# stm8.net
KiCad netlist of a schematic drawn in Altium Designer
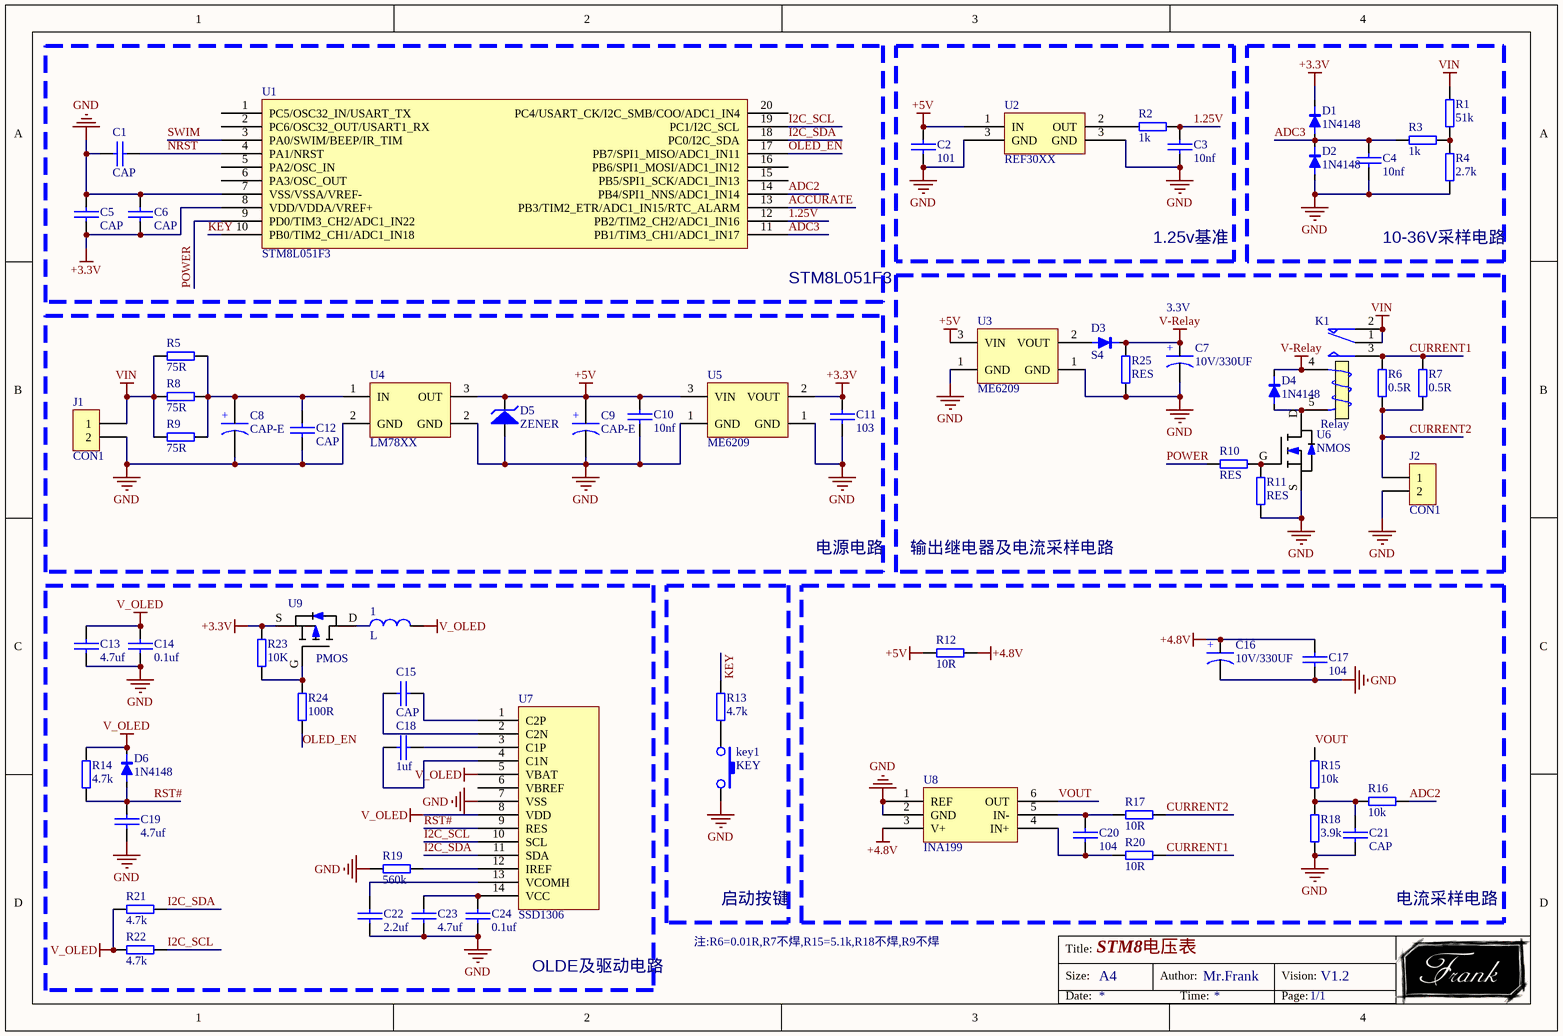
[diagram p0: stm8电压表.SchDoc]

(export (version "E")
  (design (tool "Eeschema 10.0.6"))
  (components
    (comp (ref "1") (value "L") (footprint "0603-R") (libsource (lib "常用元件库") (part "L")))
    (comp (ref "C1") (value "CAP") (footprint "0603-c") (libsource (lib "常用元件库") (part "CAP")))
    (comp (ref "C2") (value "101") (footprint "0603-c") (libsource (lib "常用元件库") (part "CAP")))
    (comp (ref "C3") (value "10nf") (footprint "0603-c") (libsource (lib "常用元件库") (part "CAP")))
    (comp (ref "C4") (value "10nf") (footprint "0603-c") (libsource (lib "常用元件库") (part "CAP")))
    (comp (ref "C5") (value "CAP") (footprint "0603-c") (libsource (lib "常用元件库") (part "CAP")))
    (comp (ref "C6") (value "CAP") (footprint "0603-c") (libsource (lib "常用元件库") (part "CAP")))
    (comp (ref "C7") (value "10V/330UF") (footprint "SMD-EC-F6.3") (libsource (lib "") (part "CAP-E_1")))
    (comp (ref "C8") (value "CAP-E") (footprint "0.1UF") (libsource (lib "常用元件库") (part "CAP-E")))
    (comp (ref "C9") (value "CAP-E") (footprint "SMD-EC-F5") (libsource (lib "常用元件库") (part "CAP-E")))
    (comp (ref "C10") (value "10nf") (footprint "0603-c") (libsource (lib "常用元件库") (part "CAP")))
    (comp (ref "C11") (value "103") (footprint "0603-c") (libsource (lib "常用元件库") (part "CAP")))
    (comp (ref "C12") (value "CAP") (footprint "0603-c") (libsource (lib "常用元件库") (part "CAP")))
    (comp (ref "C13") (value "4.7uf") (footprint "0603-c") (libsource (lib "基本原件库") (part "CAP")))
    (comp (ref "C14") (value "0.1uf") (footprint "0603-c") (libsource (lib "基本原件库") (part "CAP")))
    (comp (ref "C15") (value "CAP") (footprint "0603-c") (libsource (lib "基本原件库") (part "CAP")))
    (comp (ref "C16") (value "10V/330UF") (footprint "SMD-EC-F3") (libsource (lib "") (part "CAP-E_1")))
    (comp (ref "C17") (value "104") (footprint "0603-c") (libsource (lib "常用元件库") (part "CAP")))
    (comp (ref "C18") (value "1uf") (footprint "0603-c") (libsource (lib "基本原件库") (part "CAP")))
    (comp (ref "C19") (value "4.7uf") (footprint "0603-c") (libsource (lib "基本原件库") (part "CAP")))
    (comp (ref "C20") (value "104") (footprint "0603-c") (libsource (lib "常用元件库") (part "CAP")))
    (comp (ref "C21") (value "CAP") (footprint "0603-c") (libsource (lib "常用元件库") (part "CAP")))
    (comp (ref "C22") (value "2.2uf") (footprint "0603-c") (libsource (lib "基本原件库") (part "CAP")))
    (comp (ref "C23") (value "4.7uf") (footprint "0603-c") (libsource (lib "基本原件库") (part "CAP")))
    (comp (ref "C24") (value "0.1uf") (footprint "0603-c") (libsource (lib "基本原件库") (part "CAP")))
    (comp (ref "D1") (value "1N4148") (footprint "SOD-323") (libsource (lib "常用元件库") (part "DIODE1")))
    (comp (ref "D2") (value "1N4148") (footprint "SOD-323") (libsource (lib "常用元件库") (part "DIODE1")))
    (comp (ref "D3") (value "S4") (footprint "SOD-323") (libsource (lib "常用元件库") (part "DIODE1")))
    (comp (ref "D4") (value "1N4148") (footprint "SOD-323") (libsource (lib "常用元件库") (part "DIODE1")))
    (comp (ref "D5") (value "ZENER") (footprint "2512-d") (libsource (lib "常用元件库") (part "ZENER")))
    (comp (ref "D6") (value "1N4148") (footprint "SOD-323") (libsource (lib "常用元件库") (part "DIODE1")))
    (comp (ref "J1") (value "CON1") (footprint "SIP2") (libsource (lib "") (part "CON2_1")))
    (comp (ref "J2") (value "CON1") (footprint "SIP2") (libsource (lib "常用元件库") (part "CON2")))
    (comp (ref "K1")
      (value "Relay")
      (footprint "继电器10.5*15.5")
      (description "SPDT Relay")
      (fields (field (name "PUBLISHER") "Altium Limited"))
      (libsource (lib "Miscellaneous Devices") (part "Relay"))
    )
    (comp (ref "key1") (value "KEY") (footprint "按钮2") (libsource (lib "基本原件库") (part "KEY")))
    (comp (ref "R1") (value "51k") (footprint "0603-r") (libsource (lib "常用元件库") (part "RES")))
    (comp (ref "R2") (value "1k") (footprint "0603-r") (libsource (lib "常用元件库") (part "RES")))
    (comp (ref "R3") (value "1k") (footprint "0603-r") (libsource (lib "常用元件库") (part "RES")))
    (comp (ref "R4") (value "2.7k") (footprint "0603-r") (libsource (lib "常用元件库") (part "RES")))
    (comp (ref "R5") (value "75R") (footprint "2512-d") (libsource (lib "常用元件库") (part "RES")))
    (comp (ref "R6") (value "0.5R") (footprint "2512-D") (libsource (lib "常用元件库") (part "RES")))
    (comp (ref "R7") (value "0.5R") (footprint "2512-D") (libsource (lib "常用元件库") (part "RES")))
    (comp (ref "R8") (value "75R") (footprint "2512-d") (libsource (lib "常用元件库") (part "RES")))
    (comp (ref "R9") (value "75R") (footprint "2512-d") (libsource (lib "常用元件库") (part "RES")))
    (comp (ref "R10") (value "RES") (footprint "0603-r") (libsource (lib "常用元件库") (part "RES")))
    (comp (ref "R11") (value "RES") (footprint "0603-r") (libsource (lib "常用元件库") (part "RES")))
    (comp (ref "R12") (value "10R") (footprint "0603-r") (libsource (lib "常用元件库") (part "RES")))
    (comp (ref "R13") (value "4.7k") (footprint "0603-r") (libsource (lib "基本原件库") (part "RES")))
    (comp (ref "R14") (value "4.7k") (footprint "0603-r") (libsource (lib "基本原件库") (part "RES")))
    (comp (ref "R15") (value "10k") (footprint "0603-r") (libsource (lib "常用元件库") (part "RES")))
    (comp (ref "R16") (value "10k") (footprint "0603-r") (libsource (lib "常用元件库") (part "RES")))
    (comp (ref "R17") (value "10R") (footprint "0603-r") (libsource (lib "常用元件库") (part "RES")))
    (comp (ref "R18") (value "3.9k") (footprint "0603-r") (libsource (lib "常用元件库") (part "RES")))
    (comp (ref "R19") (value "560k") (footprint "0603-r") (libsource (lib "基本原件库") (part "RES")))
    (comp (ref "R20") (value "10R") (footprint "0603-r") (libsource (lib "常用元件库") (part "RES")))
    (comp (ref "R21") (value "4.7k") (footprint "0603-r") (libsource (lib "基本原件库") (part "RES")))
    (comp (ref "R22") (value "4.7k") (footprint "0603-r") (libsource (lib "基本原件库") (part "RES")))
    (comp (ref "R23") (value "10K") (footprint "0603-r") (libsource (lib "基本原件库") (part "RES")))
    (comp (ref "R24") (value "100R") (footprint "0603-r") (libsource (lib "基本原件库") (part "RES")))
    (comp (ref "R25") (value "RES") (footprint "0603-r") (libsource (lib "常用元件库") (part "RES")))
    (comp (ref "U1") (value "STM8L051F3") (footprint "TSSOP-20") (libsource (lib "STM8") (part "STM8L051F3")))
    (comp (ref "U2") (value "REF30XX") (footprint "SOT23") (libsource (lib "常用元件库") (part "REF30XX")))
    (comp (ref "U3") (value "ME6209") (footprint "SOT23") (libsource (lib "自定义原件库") (part "ME6209")))
    (comp (ref "U4") (value "LM78XX") (footprint "TO-252") (libsource (lib "自定义原件库") (part "LM78xx")))
    (comp (ref "U5") (value "ME6209") (footprint "SOT23") (libsource (lib "自定义原件库") (part "ME6209")))
    (comp (ref "U6") (value "NMOS") (footprint "SOT23") (libsource (lib "基本原件库") (part "NMOS")))
    (comp (ref "U7")
      (value "SSD1306")
      (footprint "OLED 0.91寸(裸屏)")
      (description "OLED屏幕")
      (libsource (lib "自定义原件库") (part "SSD1306"))
    )
    (comp (ref "U8") (value "INA199") (footprint "SOT-363") (libsource (lib "自定义原件库") (part "INA199")))
    (comp (ref "U9") (value "PMOS") (footprint "SOT23") (libsource (lib "常用元件库") (part "PMOS")))
  )
  (nets
    (net (code "1") (name "+3.3V") (class "Default")
      (node (ref "C11") (pin "1") (pinfunction "1_1") (pintype "passive"))
      (node (ref "C5") (pin "2") (pinfunction "2_2") (pintype "passive"))
      (node (ref "C6") (pin "2") (pinfunction "2_2") (pintype "passive"))
      (node (ref "D1") (pin "K") (pinfunction "K_K") (pintype "passive"))
      (node (ref "R23") (pin "2") (pinfunction "2_2") (pintype "passive"))
      (node (ref "U1") (pin "8") (pinfunction "VDD/VDDA/VREF+_8") (pintype "passive"))
      (node (ref "U5") (pin "2") (pinfunction "VOUT_2") (pintype "passive"))
      (node (ref "U9") (pin "S") (pinfunction "S_S") (pintype "passive"))
    )
    (net (code "2") (name "+4.8V") (class "Default")
      (node (ref "C16") (pin "1") (pinfunction "A_1") (pintype "passive"))
      (node (ref "C17") (pin "2") (pinfunction "2_2") (pintype "passive"))
      (node (ref "R12") (pin "2") (pinfunction "2_2") (pintype "passive"))
      (node (ref "U8") (pin "3") (pinfunction "V+_3") (pintype "passive"))
    )
    (net (code "3") (name "+5V") (class "Default")
      (node (ref "C10") (pin "1") (pinfunction "1_1") (pintype "passive"))
      (node (ref "C2") (pin "1") (pinfunction "1_1") (pintype "passive"))
      (node (ref "C9") (pin "1") (pinfunction "A_1") (pintype "passive"))
      (node (ref "D5") (pin "2") (pinfunction "K_2") (pintype "passive"))
      (node (ref "R12") (pin "1") (pinfunction "1_1") (pintype "passive"))
      (node (ref "U2") (pin "1") (pinfunction "IN_1") (pintype "passive"))
      (node (ref "U3") (pin "3") (pinfunction "VIN_3") (pintype "passive"))
      (node (ref "U4") (pin "3") (pinfunction "OUT_3") (pintype "passive"))
      (node (ref "U5") (pin "3") (pinfunction "VIN_3") (pintype "passive"))
    )
    (net (code "4") (name "/1.25V") (class "Default")
      (node (ref "C3") (pin "1") (pinfunction "1_1") (pintype "passive"))
      (node (ref "R2") (pin "2") (pinfunction "2_2") (pintype "passive"))
      (node (ref "U1") (pin "12") (pinfunction "PB2/TIM2_CH2/ADC1_IN16_12") (pintype "passive"))
    )
    (net (code "5") (name "/ACCURATE") (class "Default")
      (node (ref "U1") (pin "13") (pinfunction "PB3/TIM2_ETR/ADC1_IN15/RTC_ALARM_13") (pintype "passive"))
    )
    (net (code "6") (name "/ADC2") (class "Default")
      (node (ref "R16") (pin "2") (pinfunction "2_2") (pintype "passive"))
      (node (ref "U1") (pin "14") (pinfunction "PB4/SPI1_NNS/ADC1_IN14_14") (pintype "passive"))
    )
    (net (code "7") (name "/ADC3") (class "Default")
      (node (ref "C4") (pin "1") (pinfunction "1_1") (pintype "passive"))
      (node (ref "D1") (pin "A") (pinfunction "A_A") (pintype "passive"))
      (node (ref "D2") (pin "K") (pinfunction "K_K") (pintype "passive"))
      (node (ref "R3") (pin "2") (pinfunction "2_2") (pintype "passive"))
      (node (ref "U1") (pin "11") (pinfunction "PB1/TIM3_CH1/ADC1_IN17_11") (pintype "passive"))
    )
    (net (code "8") (name "/CURRENT1") (class "Default")
      (node (ref "K1") (pin "3") (pinfunction "NO_3") (pintype "passive"))
      (node (ref "R20") (pin "2") (pinfunction "2_2") (pintype "passive"))
      (node (ref "R6") (pin "2") (pinfunction "2_2") (pintype "passive"))
      (node (ref "R7") (pin "2") (pinfunction "2_2") (pintype "passive"))
    )
    (net (code "9") (name "/CURRENT2") (class "Default")
      (node (ref "J2") (pin "1") (pinfunction "1_1") (pintype "passive"))
      (node (ref "R17") (pin "2") (pinfunction "2_2") (pintype "passive"))
      (node (ref "R6") (pin "1") (pinfunction "1_1") (pintype "passive"))
      (node (ref "R7") (pin "1") (pinfunction "1_1") (pintype "passive"))
    )
    (net (code "10") (name "/I2C_SCL") (class "Default")
      (node (ref "R22") (pin "2") (pinfunction "2_2") (pintype "passive"))
      (node (ref "U1") (pin "19") (pinfunction "PC1/I2C_SCL_19") (pintype "passive"))
      (node (ref "U7") (pin "10") (pinfunction "SCL_10") (pintype "passive"))
    )
    (net (code "11") (name "/I2C_SDA") (class "Default")
      (node (ref "R21") (pin "2") (pinfunction "2_2") (pintype "passive"))
      (node (ref "U1") (pin "18") (pinfunction "PC0/I2C_SDA_18") (pintype "passive"))
      (node (ref "U7") (pin "11") (pinfunction "SDA_11") (pintype "passive"))
    )
    (net (code "12") (name "/KEY") (class "Default")
      (node (ref "R13") (pin "1") (pinfunction "1_1") (pintype "passive"))
      (node (ref "U1") (pin "10") (pinfunction "PB0/TIM2_CH1/ADC1_IN18_10") (pintype "passive"))
    )
    (net (code "13") (name "/NRST") (class "Default")
      (node (ref "C1") (pin "2") (pinfunction "2_2") (pintype "passive"))
      (node (ref "U1") (pin "4") (pinfunction "PA1/NRST_4") (pintype "passive"))
    )
    (net (code "14") (name "/OLED_EN") (class "Default")
      (node (ref "R24") (pin "1") (pinfunction "1_1") (pintype "passive"))
      (node (ref "U1") (pin "17") (pinfunction "PB7/SPI1_MISO/ADC1_IN11_17") (pintype "passive"))
    )
    (net (code "15") (name "/POWER") (class "Default")
      (node (ref "R10") (pin "1") (pinfunction "1_1") (pintype "passive"))
      (node (ref "U1") (pin "9") (pinfunction "PD0/TIM3_CH2/ADC1_IN22_9") (pintype "passive"))
    )
    (net (code "16") (name "/RST#") (class "Default")
      (node (ref "C19") (pin "2") (pinfunction "2_2") (pintype "passive"))
      (node (ref "D6") (pin "A") (pinfunction "A_A") (pintype "passive"))
      (node (ref "R14") (pin "2") (pinfunction "2_2") (pintype "passive"))
      (node (ref "U7") (pin "9") (pinfunction "RES_9") (pintype "passive"))
    )
    (net (code "17") (name "/SWIM") (class "Default")
      (node (ref "U1") (pin "3") (pinfunction "PA0/SWIM/BEEP/IR_TIM_3") (pintype "passive"))
    )
    (net (code "18") (name "/VOUT") (class "Default")
      (node (ref "R15") (pin "1") (pinfunction "1_1") (pintype "passive"))
      (node (ref "U8") (pin "6") (pinfunction "OUT_6") (pintype "passive"))
    )
    (net (code "19") (name "GND") (class "Default")
      (node (ref "C1") (pin "1") (pinfunction "1_1") (pintype "passive"))
      (node (ref "C10") (pin "2") (pinfunction "2_2") (pintype "passive"))
      (node (ref "C11") (pin "2") (pinfunction "2_2") (pintype "passive"))
      (node (ref "C12") (pin "2") (pinfunction "2_2") (pintype "passive"))
      (node (ref "C13") (pin "1") (pinfunction "1_1") (pintype "passive"))
      (node (ref "C14") (pin "1") (pinfunction "1_1") (pintype "passive"))
      (node (ref "C16") (pin "2") (pinfunction "C_2") (pintype "passive"))
      (node (ref "C17") (pin "1") (pinfunction "1_1") (pintype "passive"))
      (node (ref "C19") (pin "1") (pinfunction "1_1") (pintype "passive"))
      (node (ref "C2") (pin "2") (pinfunction "2_2") (pintype "passive"))
      (node (ref "C21") (pin "2") (pinfunction "2_2") (pintype "passive"))
      (node (ref "C22") (pin "1") (pinfunction "1_1") (pintype "passive"))
      (node (ref "C23") (pin "1") (pinfunction "1_1") (pintype "passive"))
      (node (ref "C24") (pin "1") (pinfunction "1_1") (pintype "passive"))
      (node (ref "C3") (pin "2") (pinfunction "2_2") (pintype "passive"))
      (node (ref "C4") (pin "2") (pinfunction "2_2") (pintype "passive"))
      (node (ref "C5") (pin "1") (pinfunction "1_1") (pintype "passive"))
      (node (ref "C6") (pin "1") (pinfunction "1_1") (pintype "passive"))
      (node (ref "C7") (pin "2") (pinfunction "C_2") (pintype "passive"))
      (node (ref "C8") (pin "2") (pinfunction "C_2") (pintype "passive"))
      (node (ref "C9") (pin "2") (pinfunction "C_2") (pintype "passive"))
      (node (ref "D2") (pin "A") (pinfunction "A_A") (pintype "passive"))
      (node (ref "D5") (pin "1") (pinfunction "A_1") (pintype "passive"))
      (node (ref "J1") (pin "2") (pinfunction "2_2") (pintype "passive"))
      (node (ref "J2") (pin "2") (pinfunction "2_2") (pintype "passive"))
      (node (ref "R11") (pin "1") (pinfunction "1_1") (pintype "passive"))
      (node (ref "R18") (pin "2") (pinfunction "2_2") (pintype "passive"))
      (node (ref "R19") (pin "2") (pinfunction "2_2") (pintype "passive"))
      (node (ref "R25") (pin "1") (pinfunction "1_1") (pintype "passive"))
      (node (ref "R4") (pin "1") (pinfunction "1_1") (pintype "passive"))
      (node (ref "U1") (pin "7") (pinfunction "VSS/VSSA/VREF-_7") (pintype "passive"))
      (node (ref "U2") (pin "3") (pinfunction "GND_3") (pintype "open_collector"))
      (node (ref "U3") (pin "1") (pinfunction "GND_1") (pintype "passive"))
      (node (ref "U4") (pin "2") (pinfunction "GND_2") (pintype "passive"))
      (node (ref "U5") (pin "1") (pinfunction "GND_1") (pintype "passive"))
      (node (ref "U6") (pin "S") (pinfunction "S_S") (pintype "passive"))
      (node (ref "U7") (pin "7") (pinfunction "VSS_7") (pintype "passive"))
      (node (ref "U8") (pin "1") (pinfunction "REF_1") (pintype "passive"))
      (node (ref "U8") (pin "2") (pinfunction "GND_2") (pintype "passive"))
      (node (ref "key1") (pin "2") (pinfunction "2_2") (pintype "passive"))
    )
    (net (code "20") (name "Net-(1-Pad2)") (class "Default")
      (node (ref "1") (pin "2") (pinfunction "2_2") (pintype "passive"))
      (node (ref "U9") (pin "D") (pinfunction "D_D") (pintype "passive"))
    )
    (net (code "21") (name "Net-(C8-A)") (class "Default")
      (node (ref "C12") (pin "1") (pinfunction "1_1") (pintype "passive"))
      (node (ref "C8") (pin "1") (pinfunction "A_1") (pintype "passive"))
      (node (ref "R5") (pin "2") (pinfunction "2_2") (pintype "passive"))
      (node (ref "R8") (pin "2") (pinfunction "2_2") (pintype "passive"))
      (node (ref "R9") (pin "2") (pinfunction "2_2") (pintype "passive"))
      (node (ref "U4") (pin "1") (pinfunction "IN_1") (pintype "passive"))
    )
    (net (code "22") (name "Net-(C21-Pad1)") (class "Default")
      (node (ref "C21") (pin "1") (pinfunction "1_1") (pintype "passive"))
      (node (ref "R15") (pin "2") (pinfunction "2_2") (pintype "passive"))
      (node (ref "R16") (pin "1") (pinfunction "1_1") (pintype "passive"))
      (node (ref "R18") (pin "1") (pinfunction "1_1") (pintype "passive"))
    )
    (net (code "23") (name "Net-(K1-T2)") (class "Default")
      (node (ref "D4") (pin "A") (pinfunction "A_A") (pintype "passive"))
      (node (ref "K1") (pin "5") (pinfunction "T2_5") (pintype "passive"))
      (node (ref "U6") (pin "D") (pinfunction "D_D") (pintype "passive"))
    )
    (net (code "24") (name "Net-(R1-Pad2)") (class "Default")
      (node (ref "R1") (pin "2") (pinfunction "2_2") (pintype "passive"))
      (node (ref "R3") (pin "1") (pinfunction "1_1") (pintype "passive"))
      (node (ref "R4") (pin "2") (pinfunction "2_2") (pintype "passive"))
    )
    (net (code "25") (name "Net-(R10-Pad2)") (class "Default")
      (node (ref "R10") (pin "2") (pinfunction "2_2") (pintype "passive"))
      (node (ref "R11") (pin "2") (pinfunction "2_2") (pintype "passive"))
      (node (ref "U6") (pin "G") (pinfunction "G_G") (pintype "passive"))
    )
    (net (code "26") (name "Net-(R13-Pad2)") (class "Default")
      (node (ref "R13") (pin "2") (pinfunction "2_2") (pintype "passive"))
      (node (ref "key1") (pin "1") (pinfunction "1_1") (pintype "passive"))
    )
    (net (code "27") (name "Net-(R23-Pad1)") (class "Default")
      (node (ref "R23") (pin "1") (pinfunction "1_1") (pintype "passive"))
      (node (ref "R24") (pin "2") (pinfunction "2_2") (pintype "passive"))
      (node (ref "U9") (pin "G") (pinfunction "G_G") (pintype "passive"))
    )
    (net (code "28") (name "Net-(U2-OUT)") (class "Default")
      (node (ref "R2") (pin "1") (pinfunction "1_1") (pintype "passive"))
      (node (ref "U2") (pin "2") (pinfunction "OUT_2") (pintype "passive"))
    )
    (net (code "29") (name "Net-(U3-VOUT)") (class "Default")
      (node (ref "D3") (pin "A") (pinfunction "A_A") (pintype "passive"))
      (node (ref "U3") (pin "2") (pinfunction "VOUT_2") (pintype "passive"))
    )
    (net (code "30") (name "Net-(U7-C1N)") (class "Default")
      (node (ref "C18") (pin "1") (pinfunction "1_1") (pintype "passive"))
      (node (ref "U7") (pin "4") (pinfunction "C1N_4") (pintype "passive"))
    )
    (net (code "31") (name "Net-(U7-C1P)") (class "Default")
      (node (ref "C18") (pin "2") (pinfunction "2_2") (pintype "passive"))
      (node (ref "U7") (pin "3") (pinfunction "C1P_3") (pintype "passive"))
    )
    (net (code "32") (name "Net-(U7-C2N)") (class "Default")
      (node (ref "C15") (pin "1") (pinfunction "1_1") (pintype "passive"))
      (node (ref "U7") (pin "2") (pinfunction "C2N_2") (pintype "passive"))
    )
    (net (code "33") (name "Net-(U7-C2P)") (class "Default")
      (node (ref "C15") (pin "2") (pinfunction "2_2") (pintype "passive"))
      (node (ref "U7") (pin "1") (pinfunction "C2P_1") (pintype "passive"))
    )
    (net (code "34") (name "Net-(U7-IREF)") (class "Default")
      (node (ref "R19") (pin "1") (pinfunction "1_1") (pintype "passive"))
      (node (ref "U7") (pin "12") (pinfunction "IREF_12") (pintype "passive"))
    )
    (net (code "35") (name "Net-(U7-VCC)") (class "Default")
      (node (ref "C23") (pin "2") (pinfunction "2_2") (pintype "passive"))
      (node (ref "C24") (pin "2") (pinfunction "2_2") (pintype "passive"))
      (node (ref "U7") (pin "14") (pinfunction "VCC_14") (pintype "passive"))
    )
    (net (code "36") (name "Net-(U7-VCOMH)") (class "Default")
      (node (ref "C22") (pin "2") (pinfunction "2_2") (pintype "passive"))
      (node (ref "U7") (pin "13") (pinfunction "VCOMH_13") (pintype "passive"))
    )
    (net (code "37") (name "Net-(U8-IN+)") (class "Default")
      (node (ref "C20") (pin "1") (pinfunction "1_1") (pintype "passive"))
      (node (ref "R20") (pin "1") (pinfunction "1_1") (pintype "passive"))
      (node (ref "U8") (pin "4") (pinfunction "IN+_4") (pintype "passive"))
    )
    (net (code "38") (name "Net-(U8-IN-)") (class "Default")
      (node (ref "C20") (pin "2") (pinfunction "2_2") (pintype "passive"))
      (node (ref "R17") (pin "1") (pinfunction "1_1") (pintype "passive"))
      (node (ref "U8") (pin "5") (pinfunction "IN-_5") (pintype "passive"))
    )
    (net (code "39") (name "V-Relay") (class "Default")
      (node (ref "C7") (pin "1") (pinfunction "A_1") (pintype "passive"))
      (node (ref "D3") (pin "K") (pinfunction "K_K") (pintype "passive"))
      (node (ref "D4") (pin "K") (pinfunction "K_K") (pintype "passive"))
      (node (ref "K1") (pin "4") (pinfunction "T1_4") (pintype "passive"))
      (node (ref "R25") (pin "2") (pinfunction "2_2") (pintype "passive"))
    )
    (net (code "40") (name "VIN") (class "Default")
      (node (ref "J1") (pin "1") (pinfunction "1_1") (pintype "passive"))
      (node (ref "K1") (pin "1") (pinfunction "COM_1") (pintype "passive"))
      (node (ref "K1") (pin "2") (pinfunction "NC_2") (pintype "passive"))
      (node (ref "R1") (pin "1") (pinfunction "1_1") (pintype "passive"))
      (node (ref "R5") (pin "1") (pinfunction "1_1") (pintype "passive"))
      (node (ref "R8") (pin "1") (pinfunction "1_1") (pintype "passive"))
      (node (ref "R9") (pin "1") (pinfunction "1_1") (pintype "passive"))
    )
    (net (code "41") (name "V_OLED") (class "Default")
      (node (ref "1") (pin "1") (pinfunction "1_1") (pintype "passive"))
      (node (ref "C13") (pin "2") (pinfunction "2_2") (pintype "passive"))
      (node (ref "C14") (pin "2") (pinfunction "2_2") (pintype "passive"))
      (node (ref "D6") (pin "K") (pinfunction "K_K") (pintype "passive"))
      (node (ref "R14") (pin "1") (pinfunction "1_1") (pintype "passive"))
      (node (ref "R21") (pin "1") (pinfunction "1_1") (pintype "passive"))
      (node (ref "R22") (pin "1") (pinfunction "1_1") (pintype "passive"))
      (node (ref "U7") (pin "5") (pinfunction "VBAT_5") (pintype "passive"))
      (node (ref "U7") (pin "8") (pinfunction "VDD_8") (pintype "passive"))
    )
    (net (code "42") (name "unconnected-(U1-PA2{slash}OSC_IN-Pad5)") (class "Default")
      (node (ref "U1") (pin "5") (pinfunction "PA2/OSC_IN_5") (pintype "passive"))
    )
    (net (code "43") (name "unconnected-(U1-PA3{slash}OSC_OUT-Pad6)") (class "Default")
      (node (ref "U1") (pin "6") (pinfunction "PA3/OSC_OUT_6") (pintype "passive"))
    )
    (net (code "44") (name "unconnected-(U1-PB5{slash}SPI1_SCK{slash}ADC1_IN13-Pad15)") (class "Default")
      (node (ref "U1") (pin "15") (pinfunction "PB5/SPI1_SCK/ADC1_IN13_15") (pintype "passive"))
    )
    (net (code "45") (name "unconnected-(U1-PB6{slash}SPI1_MOSI{slash}ADC1_IN12-Pad16)") (class "Default")
      (node (ref "U1") (pin "16") (pinfunction "PB6/SPI1_MOSI/ADC1_IN12_16") (pintype "passive"))
    )
    (net (code "46") (name "unconnected-(U1-PC4{slash}USART_CK{slash}I2C_SMB{slash}COO{slash}ADC1_IN4-Pad20)") (class "Default")
      (node (ref "U1") (pin "20") (pinfunction "PC4/USART_CK/I2C_SMB/COO/ADC1_IN4_20") (pintype "passive"))
    )
    (net (code "47") (name "unconnected-(U1-PC5{slash}OSC32_IN{slash}USART_TX-Pad1)") (class "Default")
      (node (ref "U1") (pin "1") (pinfunction "PC5/OSC32_IN/USART_TX_1") (pintype "passive"))
    )
    (net (code "48") (name "unconnected-(U1-PC6{slash}OSC32_OUT{slash}USART1_RX-Pad2)") (class "Default")
      (node (ref "U1") (pin "2") (pinfunction "PC6/OSC32_OUT/USART1_RX_2") (pintype "passive"))
    )
    (net (code "49") (name "unconnected-(U7-VBREF-Pad6)") (class "Default")
      (node (ref "U7") (pin "6") (pinfunction "VBREF_6") (pintype "passive"))
    )
  )
)
